# finalFilter2.net
KiCad netlist of a schematic drawn in Altium Designer
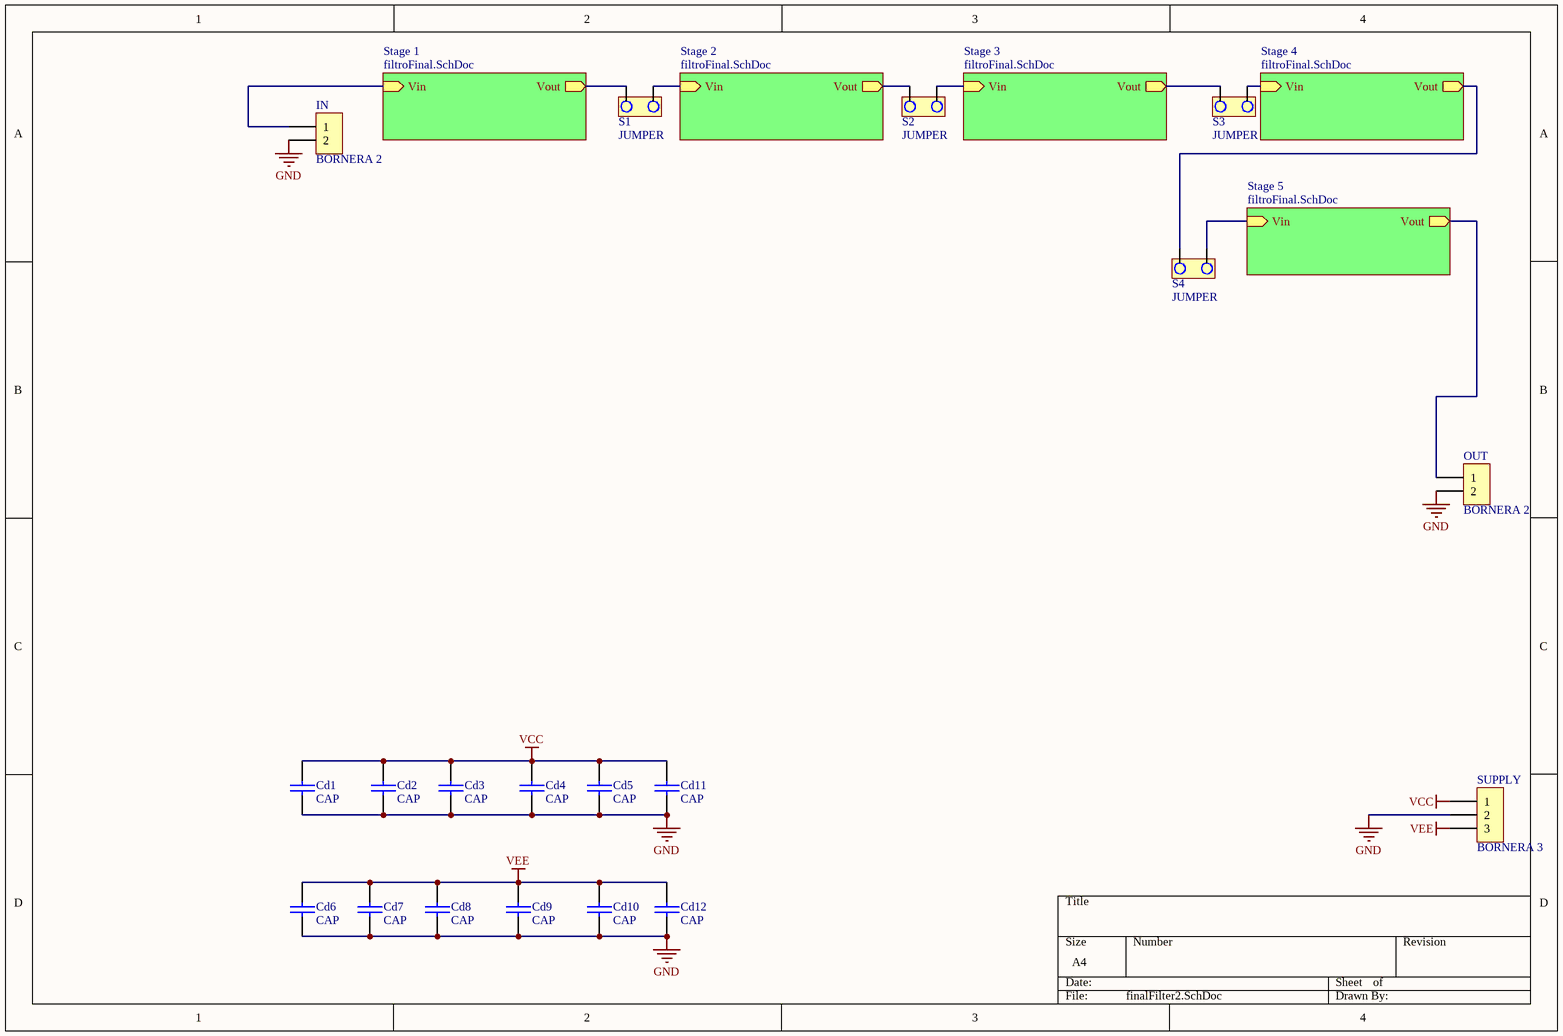
[diagram p0: finalFilter2.SchDoc]

(export (version "E")
  (design (tool "Eeschema 10.0.6"))
  (components
    (comp (ref "Cd1") (value "CAP") (footprint "CAP200") (libsource (lib "LIBEBAL") (part "CAP")))
    (comp (ref "Cd2") (value "CAP") (footprint "CAP200") (libsource (lib "LIBEBAL") (part "CAP")))
    (comp (ref "Cd3") (value "CAP") (footprint "CAP200") (libsource (lib "LIBEBAL") (part "CAP")))
    (comp (ref "Cd4") (value "CAP") (footprint "CAP200") (libsource (lib "LIBEBAL") (part "CAP")))
    (comp (ref "Cd5") (value "CAP") (footprint "CAP200") (libsource (lib "LIBEBAL") (part "CAP")))
    (comp (ref "Cd6") (value "CAP") (footprint "CAP200") (libsource (lib "LIBEBAL") (part "CAP")))
    (comp (ref "Cd7") (value "CAP") (footprint "CAP200") (libsource (lib "LIBEBAL") (part "CAP")))
    (comp (ref "Cd8") (value "CAP") (footprint "CAP200") (libsource (lib "LIBEBAL") (part "CAP")))
    (comp (ref "Cd9") (value "CAP") (footprint "CAP200") (libsource (lib "LIBEBAL") (part "CAP")))
    (comp (ref "Cd10") (value "CAP") (footprint "CAP200") (libsource (lib "LIBEBAL") (part "CAP")))
    (comp (ref "Cd11") (value "CAP") (footprint "CAP200") (libsource (lib "LIBEBAL") (part "CAP")))
    (comp (ref "Cd12") (value "CAP") (footprint "CAP200") (libsource (lib "LIBEBAL") (part "CAP")))
    (comp (ref "IN")
      (value "BORNERA 2")
      (footprint "BORNERA2")
      (libsource (lib "LIBEBAL") (part "BORNERA 2"))
    )
    (comp (ref "OUT")
      (value "BORNERA 2")
      (footprint "BORNERA2")
      (libsource (lib "LIBEBAL") (part "BORNERA 2"))
    )
    (comp (ref "S1") (value "JUMPER") (footprint "JUMPER2") (libsource (lib "LIBEBAL") (part "JUMPER")))
    (comp (ref "S2") (value "JUMPER") (footprint "JUMPER2") (libsource (lib "LIBEBAL") (part "JUMPER")))
    (comp (ref "S3") (value "JUMPER") (footprint "JUMPER2") (libsource (lib "LIBEBAL") (part "JUMPER")))
    (comp (ref "S4") (value "JUMPER") (footprint "JUMPER2") (libsource (lib "LIBEBAL") (part "JUMPER")))
    (comp (ref "SUPPLY")
      (value "BORNERA 3")
      (footprint "BORNERA3")
      (libsource (lib "LIBEBAL") (part "BORNERA 3"))
    )
  )
  (nets
    (net (code "1") (name "/Vin") (class "Default")
      (node (ref "IN") (pin "1") (pinfunction "1_1") (pintype "passive"))
    )
    (net (code "2") (name "/Vin_1") (class "Default")
      (node (ref "S1") (pin "2") (pinfunction "2_2") (pintype "passive"))
    )
    (net (code "3") (name "/Vin_2") (class "Default")
      (node (ref "S2") (pin "2") (pinfunction "2_2") (pintype "passive"))
    )
    (net (code "4") (name "/Vin_3") (class "Default")
      (node (ref "S3") (pin "2") (pinfunction "2_2") (pintype "passive"))
    )
    (net (code "5") (name "/Vin_4") (class "Default")
      (node (ref "S4") (pin "2") (pinfunction "2_2") (pintype "passive"))
    )
    (net (code "6") (name "/Vout") (class "Default")
      (node (ref "OUT") (pin "1") (pinfunction "1_1") (pintype "passive"))
    )
    (net (code "7") (name "/Vout_1") (class "Default")
      (node (ref "S2") (pin "1") (pinfunction "1_1") (pintype "passive"))
    )
    (net (code "8") (name "/Vout_2") (class "Default")
      (node (ref "S4") (pin "1") (pinfunction "1_1") (pintype "passive"))
    )
    (net (code "9") (name "/Vout_3") (class "Default")
      (node (ref "S3") (pin "1") (pinfunction "1_1") (pintype "passive"))
    )
    (net (code "10") (name "/Vout_4") (class "Default")
      (node (ref "S1") (pin "1") (pinfunction "1_1") (pintype "passive"))
    )
    (net (code "11") (name "GND") (class "Default")
      (node (ref "Cd1") (pin "2") (pinfunction "2_2") (pintype "passive"))
      (node (ref "Cd10") (pin "2") (pinfunction "2_2") (pintype "passive"))
      (node (ref "Cd11") (pin "2") (pinfunction "2_2") (pintype "passive"))
      (node (ref "Cd12") (pin "2") (pinfunction "2_2") (pintype "passive"))
      (node (ref "Cd2") (pin "2") (pinfunction "2_2") (pintype "passive"))
      (node (ref "Cd3") (pin "2") (pinfunction "2_2") (pintype "passive"))
      (node (ref "Cd4") (pin "2") (pinfunction "2_2") (pintype "passive"))
      (node (ref "Cd5") (pin "2") (pinfunction "2_2") (pintype "passive"))
      (node (ref "Cd6") (pin "2") (pinfunction "2_2") (pintype "passive"))
      (node (ref "Cd7") (pin "2") (pinfunction "2_2") (pintype "passive"))
      (node (ref "Cd8") (pin "2") (pinfunction "2_2") (pintype "passive"))
      (node (ref "Cd9") (pin "2") (pinfunction "2_2") (pintype "passive"))
      (node (ref "IN") (pin "2") (pinfunction "2_2") (pintype "passive"))
      (node (ref "OUT") (pin "2") (pinfunction "2_2") (pintype "passive"))
      (node (ref "SUPPLY") (pin "2") (pinfunction "2_2") (pintype "passive"))
    )
    (net (code "12") (name "VCC") (class "Default")
      (node (ref "Cd1") (pin "1") (pinfunction "1_1") (pintype "passive"))
      (node (ref "Cd11") (pin "1") (pinfunction "1_1") (pintype "passive"))
      (node (ref "Cd2") (pin "1") (pinfunction "1_1") (pintype "passive"))
      (node (ref "Cd3") (pin "1") (pinfunction "1_1") (pintype "passive"))
      (node (ref "Cd4") (pin "1") (pinfunction "1_1") (pintype "passive"))
      (node (ref "Cd5") (pin "1") (pinfunction "1_1") (pintype "passive"))
      (node (ref "SUPPLY") (pin "1") (pinfunction "1_1") (pintype "passive"))
    )
    (net (code "13") (name "VEE") (class "Default")
      (node (ref "Cd10") (pin "1") (pinfunction "1_1") (pintype "passive"))
      (node (ref "Cd12") (pin "1") (pinfunction "1_1") (pintype "passive"))
      (node (ref "Cd6") (pin "1") (pinfunction "1_1") (pintype "passive"))
      (node (ref "Cd7") (pin "1") (pinfunction "1_1") (pintype "passive"))
      (node (ref "Cd8") (pin "1") (pinfunction "1_1") (pintype "passive"))
      (node (ref "Cd9") (pin "1") (pinfunction "1_1") (pintype "passive"))
      (node (ref "SUPPLY") (pin "3") (pinfunction "3_3") (pintype "passive"))
    )
  )
)
